# CH32V203F6P6-R0.net
KiCad netlist of a schematic drawn in Altium Designer
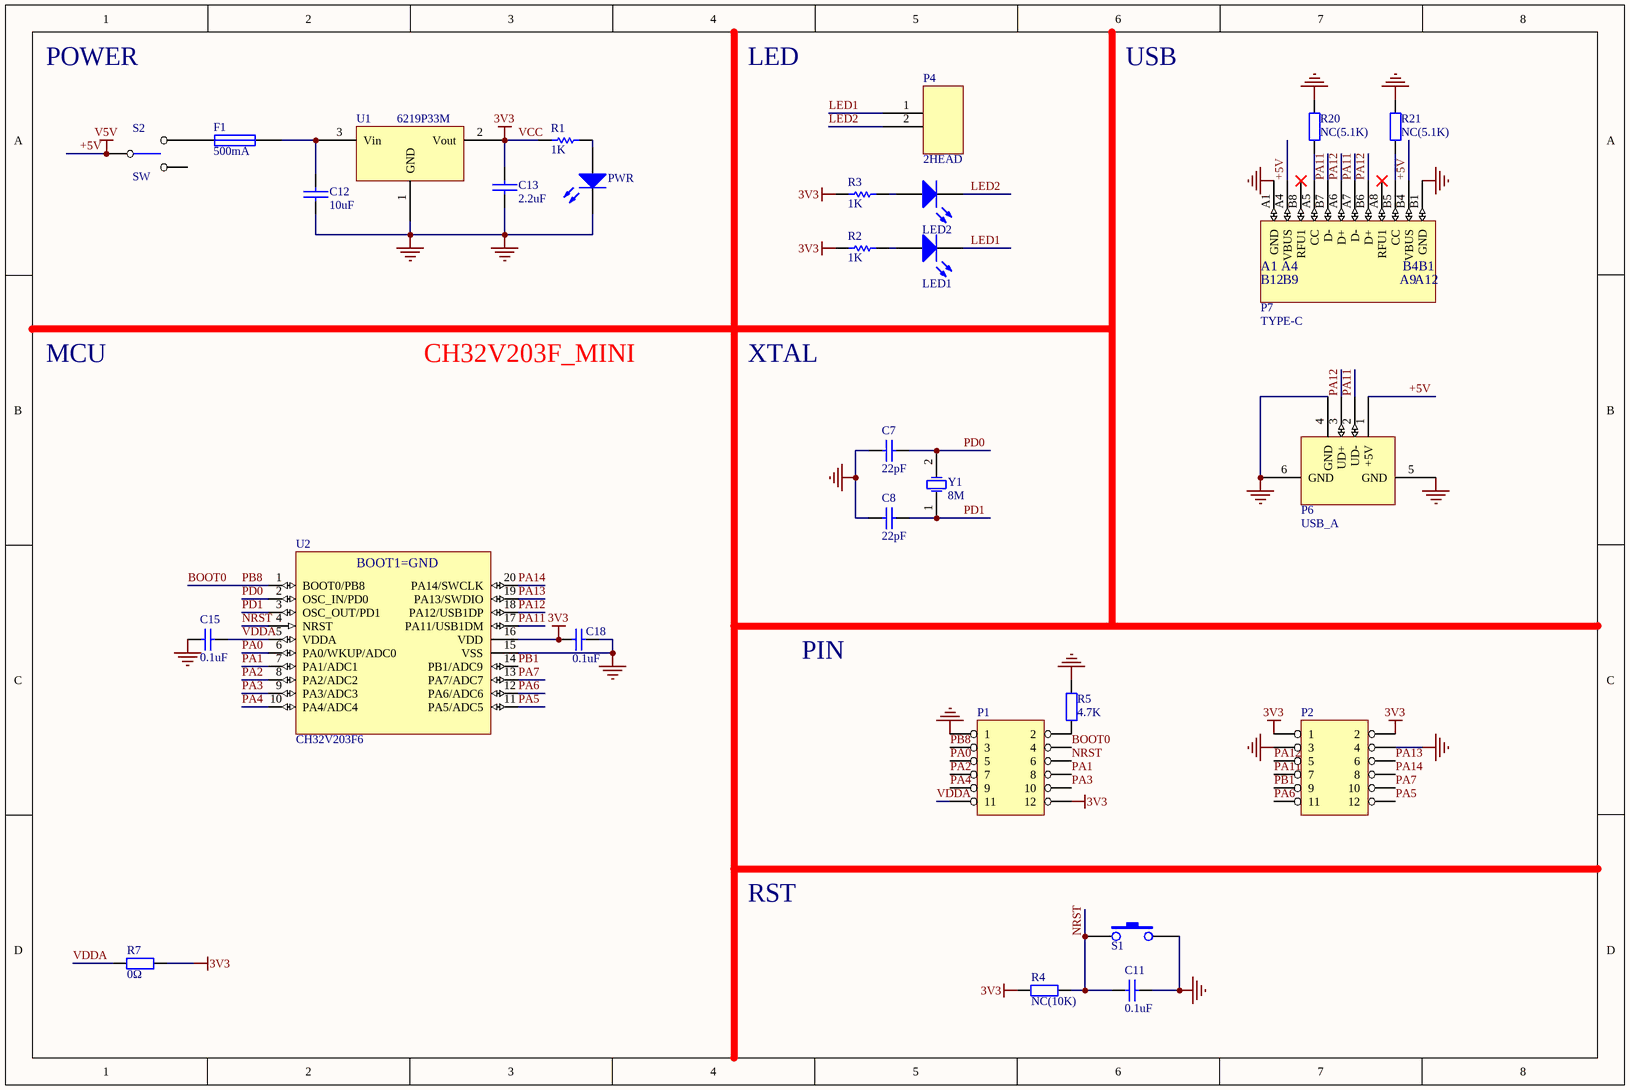
[diagram p0: CH32V203F6P6-R0.SchDoc]

(export (version "E")
  (design (tool "Eeschema 10.0.6"))
  (components
    (comp (ref "C7")
      (value "22pF")
      (footprint "0603_C")
      (description "Capacitor")
      (fields (field (name "PUBLISHER") "Altium Limited"))
      (libsource (lib "*") (part "Cap"))
    )
    (comp (ref "C8")
      (value "22pF")
      (footprint "0603_C")
      (description "Capacitor")
      (fields (field (name "PUBLISHER") "Altium Limited"))
      (libsource (lib "*") (part "Cap"))
    )
    (comp (ref "C11")
      (value "0.1uF")
      (footprint "0603_C")
      (description "Capacitor")
      (fields (field (name "PUBLISHER") "Altium Limited"))
      (libsource (lib "*") (part "Cap"))
    )
    (comp (ref "C12")
      (value "10uF")
      (footprint "3216_C")
      (description "Capacitor")
      (libsource (lib "wch_sch_others") (part "CAP"))
    )
    (comp (ref "C13")
      (value "2.2uF")
      (footprint "0603_C")
      (description "Capacitor")
      (libsource (lib "wch_sch_others") (part "CAP"))
    )
    (comp (ref "C15")
      (value "0.1uF")
      (footprint "0603_C")
      (description "Capacitor")
      (fields (field (name "PUBLISHER") "Altium Limited"))
      (libsource (lib "*") (part "Cap"))
    )
    (comp (ref "C18")
      (value "0.1uF")
      (footprint "0603_C")
      (description "Capacitor")
      (fields (field (name "PUBLISHER") "Altium Limited"))
      (libsource (lib "*") (part "Cap"))
    )
    (comp (ref "F1")
      (value "500mA")
      (footprint "0603")
      (description "Fuse")
      (libsource (lib "*") (part "FUSE1"))
    )
    (comp (ref "LED1")
      (value "LED1   blue")
      (footprint "0603+")
      (description "Typical INFRARED GaAs LED")
      (fields (field (name "PUBLISHER") "Altium Limited"))
      (libsource (lib "*") (part "LED0"))
    )
    (comp (ref "LED2")
      (value "LED2  blue")
      (footprint "0603+")
      (description "Typical INFRARED GaAs LED")
      (fields (field (name "PUBLISHER") "Altium Limited"))
      (libsource (lib "*") (part "LED0"))
    )
    (comp (ref "P1")
      (value "HEADER 6x2")
      (footprint "MYPCB:IDC12-2.54mm")
      (description "Header, 6-Pin, Dual row")
      (libsource (lib "wch_sch_others") (part "HEADER 6x2"))
    )
    (comp (ref "P2")
      (value "HEADER 6x2")
      (footprint "MYPCB:IDC12-2.54mm")
      (description "Header, 6-Pin, Dual row")
      (libsource (lib "wch_sch_others") (part "HEADER 6x2"))
    )
    (comp (ref "P4") (value "2HEAD") (footprint "SIP2-2.54mm") (libsource (lib "*") (part "2HEAD")))
    (comp (ref "P6")
      (value "USB_A")
      (footprint "USBAF")
      (description "USB Port")
      (libsource (lib "*") (part "USB"))
    )
    (comp (ref "P7")
      (value "TYPE-C")
      (footprint "TYPE-C-Receptacle-2.0")
      (libsource (lib "*") (part "TYPE-C1"))
    )
    (comp (ref "PWR")
      (value "POWER  red")
      (footprint "0603+")
      (description "Typical INFRARED GaAs LED")
      (fields (field (name "PUBLISHER") "Altium Limited"))
      (libsource (lib "*") (part "LED0"))
    )
    (comp (ref "R1")
      (value "1K")
      (footprint "0603")
      (description "Semiconductor Resistor")
      (fields (field (name "PUBLISHER") "Altium Limited"))
      (libsource (lib "*") (part "Res Semi"))
    )
    (comp (ref "R2")
      (value "1K")
      (footprint "0603")
      (description "Semiconductor Resistor")
      (fields (field (name "PUBLISHER") "Altium Limited"))
      (libsource (lib "*") (part "Res Semi"))
    )
    (comp (ref "R3")
      (value "1K")
      (footprint "0603")
      (description "Semiconductor Resistor")
      (fields (field (name "PUBLISHER") "Altium Limited"))
      (libsource (lib "*") (part "Res Semi"))
    )
    (comp (ref "R4")
      (value "NC(10K)")
      (footprint "0603")
      (description "Resistor")
      (fields (field (name "PUBLISHER") "Altium Limited"))
      (libsource (lib "") (part "Res2_1"))
    )
    (comp (ref "R5")
      (value "4.7K")
      (footprint "0603")
      (description "Resistor")
      (fields (field (name "PUBLISHER") "Altium Limited"))
      (libsource (lib "*") (part "Res2"))
    )
    (comp (ref "R7")
      (value "0Ω")
      (footprint "0603")
      (description "Resistor")
      (fields (field (name "PUBLISHER") "Altium Limited"))
      (libsource (lib "") (part "Res2_1"))
    )
    (comp (ref "R20")
      (value "NC(5.1K)")
      (footprint "0603")
      (description "Resistor")
      (libsource (lib "Miscellaneous Devices") (part "Res2"))
    )
    (comp (ref "R21")
      (value "NC(5.1K)")
      (footprint "0603")
      (description "Resistor")
      (libsource (lib "Miscellaneous Devices") (part "Res2"))
    )
    (comp (ref "S1") (value "NRST") (footprint "SMD_6.1x3.65x2.5mm-KEY") (libsource (lib "*") (part "KEY")))
    (comp (ref "S2") (value "SW") (footprint "KEY2") (libsource (lib "*") (part "SW")))
    (comp (ref "U1")
      (value "6219P33M")
      (footprint "SOT-23")
      (libsource (lib "wch_sch_others") (part "6219P33M"))
    )
    (comp (ref "U2")
      (value "CH32V203F6")
      (footprint "TSSOP20")
      (description "RISC-V LMD-MCU, 144MHz, USB FS, CAN, Mul-ADC,OPA")
      (libsource (lib "CHXXX") (part "CH32V203F6"))
    )
    (comp (ref "Y1")
      (value "8M")
      (footprint "XT_AT49")
      (description "Crystal Oscillator")
      (fields (field (name "PUBLISHER") "Altium Limited"))
      (libsource (lib "*") (part "XTAL"))
    )
  )
  (nets
    (net (code "2") (name "/BOOT0") (class "Default")
      (node (ref "P1") (pin "3") (pinfunction "3_3") (pintype "passive"))
      (node (ref "P1") (pin "4") (pinfunction "4_4") (pintype "passive"))
      (node (ref "U2") (pin "1") (pinfunction "BOOT0/PB8_1") (pintype "bidirectional"))
    )
    (net (code "3") (name "/LED1") (class "Default")
      (node (ref "LED1") (pin "2") (pinfunction "K_2") (pintype "passive"))
      (node (ref "P4") (pin "1") (pintype "passive"))
    )
    (net (code "4") (name "/LED2") (class "Default")
      (node (ref "LED2") (pin "2") (pinfunction "K_2") (pintype "passive"))
      (node (ref "P4") (pin "2") (pintype "passive"))
    )
    (net (code "5") (name "/NRST") (class "Default")
      (node (ref "C11") (pin "2") (pinfunction "2_2") (pintype "passive"))
      (node (ref "P1") (pin "6") (pinfunction "6_6") (pintype "passive"))
      (node (ref "R4") (pin "1") (pinfunction "1_1") (pintype "passive"))
      (node (ref "S1") (pin "1") (pinfunction "1_1") (pintype "passive"))
      (node (ref "U2") (pin "4") (pinfunction "NRST_4") (pintype "input"))
    )
    (net (code "6") (name "/PA0") (class "Default")
      (node (ref "P1") (pin "5") (pinfunction "5_5") (pintype "passive"))
      (node (ref "U2") (pin "6") (pinfunction "PA0/WKUP/ADC0_6") (pintype "bidirectional"))
    )
    (net (code "7") (name "/PA1") (class "Default")
      (node (ref "P1") (pin "8") (pinfunction "8_8") (pintype "passive"))
      (node (ref "U2") (pin "7") (pinfunction "PA1/ADC1_7") (pintype "bidirectional"))
    )
    (net (code "8") (name "/PA2") (class "Default")
      (node (ref "P1") (pin "7") (pinfunction "7_7") (pintype "passive"))
      (node (ref "U2") (pin "8") (pinfunction "PA2/ADC2_8") (pintype "bidirectional"))
    )
    (net (code "9") (name "/PA3") (class "Default")
      (node (ref "P1") (pin "10") (pinfunction "10_10") (pintype "passive"))
      (node (ref "U2") (pin "9") (pinfunction "PA3/ADC3_9") (pintype "bidirectional"))
    )
    (net (code "10") (name "/PA4") (class "Default")
      (node (ref "P1") (pin "9") (pinfunction "9_9") (pintype "passive"))
      (node (ref "U2") (pin "10") (pinfunction "PA4/ADC4_10") (pintype "bidirectional"))
    )
    (net (code "11") (name "/PA5") (class "Default")
      (node (ref "P2") (pin "12") (pinfunction "12_12") (pintype "passive"))
      (node (ref "U2") (pin "11") (pinfunction "PA5/ADC5_11") (pintype "bidirectional"))
    )
    (net (code "12") (name "/PA6") (class "Default")
      (node (ref "P2") (pin "11") (pinfunction "11_11") (pintype "passive"))
      (node (ref "U2") (pin "12") (pinfunction "PA6/ADC6_12") (pintype "bidirectional"))
    )
    (net (code "13") (name "/PA7") (class "Default")
      (node (ref "P2") (pin "10") (pinfunction "10_10") (pintype "passive"))
      (node (ref "U2") (pin "13") (pinfunction "PA7/ADC7_13") (pintype "bidirectional"))
    )
    (net (code "14") (name "/PA11") (class "Default")
      (node (ref "P2") (pin "7") (pinfunction "7_7") (pintype "passive"))
      (node (ref "P6") (pin "2") (pinfunction "UD-_2") (pintype "bidirectional"))
      (node (ref "P7") (pin "A7") (pinfunction "D-_A7") (pintype "bidirectional"))
      (node (ref "P7") (pin "B7") (pinfunction "D-_B7") (pintype "bidirectional"))
      (node (ref "U2") (pin "17") (pinfunction "PA11/USB1DM_17") (pintype "bidirectional"))
    )
    (net (code "15") (name "/PA12") (class "Default")
      (node (ref "P2") (pin "5") (pinfunction "5_5") (pintype "passive"))
      (node (ref "P6") (pin "3") (pinfunction "UD+_3") (pintype "bidirectional"))
      (node (ref "P7") (pin "A6") (pinfunction "D+_A6") (pintype "bidirectional"))
      (node (ref "P7") (pin "B6") (pinfunction "D+_B6") (pintype "bidirectional"))
      (node (ref "U2") (pin "18") (pinfunction "PA12/USB1DP_18") (pintype "bidirectional"))
    )
    (net (code "16") (name "/PA13") (class "Default")
      (node (ref "P2") (pin "6") (pinfunction "6_6") (pintype "passive"))
      (node (ref "U2") (pin "19") (pinfunction "PA13/SWDIO_19") (pintype "bidirectional"))
    )
    (net (code "17") (name "/PA14") (class "Default")
      (node (ref "P2") (pin "8") (pinfunction "8_8") (pintype "passive"))
      (node (ref "U2") (pin "20") (pinfunction "PA14/SWCLK_20") (pintype "bidirectional"))
    )
    (net (code "18") (name "/PB1") (class "Default")
      (node (ref "P2") (pin "9") (pinfunction "9_9") (pintype "passive"))
      (node (ref "U2") (pin "14") (pinfunction "PB1/ADC9_14") (pintype "bidirectional"))
    )
    (net (code "19") (name "/PD0") (class "Default")
      (node (ref "C7") (pin "2") (pinfunction "2_2") (pintype "passive"))
      (node (ref "U2") (pin "2") (pinfunction "OSC_IN/PD0_2") (pintype "bidirectional"))
      (node (ref "Y1") (pin "2") (pinfunction "OSC2_2") (pintype "passive"))
    )
    (net (code "20") (name "/PD1") (class "Default")
      (node (ref "C8") (pin "2") (pinfunction "2_2") (pintype "passive"))
      (node (ref "U2") (pin "3") (pinfunction "OSC_OUT/PD1_3") (pintype "bidirectional"))
      (node (ref "Y1") (pin "1") (pinfunction "OSC1_1") (pintype "passive"))
    )
    (net (code "21") (name "/VDDA") (class "Default")
      (node (ref "C15") (pin "1") (pinfunction "1_1") (pintype "passive"))
      (node (ref "P1") (pin "11") (pinfunction "11_11") (pintype "passive"))
      (node (ref "R7") (pin "2") (pinfunction "2_2") (pintype "passive"))
      (node (ref "U2") (pin "5") (pinfunction "VDDA_5") (pintype "bidirectional"))
    )
    (net (code "22") (name "3V3") (class "Default")
      (node (ref "C13") (pin "2") (pinfunction "2_2") (pintype "passive"))
      (node (ref "C18") (pin "2") (pinfunction "2_2") (pintype "passive"))
      (node (ref "P1") (pin "12") (pinfunction "12_12") (pintype "passive"))
      (node (ref "P2") (pin "1") (pinfunction "1_1") (pintype "passive"))
      (node (ref "P2") (pin "2") (pinfunction "2_2") (pintype "passive"))
      (node (ref "R1") (pin "2") (pinfunction "2_2") (pintype "passive"))
      (node (ref "R2") (pin "1") (pinfunction "1_1") (pintype "passive"))
      (node (ref "R3") (pin "1") (pinfunction "1_1") (pintype "passive"))
      (node (ref "R4") (pin "2") (pinfunction "2_2") (pintype "passive"))
      (node (ref "R7") (pin "1") (pinfunction "1_1") (pintype "passive"))
      (node (ref "U1") (pin "2") (pinfunction "Vout_2") (pintype "passive"))
      (node (ref "U2") (pin "16") (pinfunction "VDD_16") (pintype "power_in"))
    )
    (net (code "23") (name "GND") (class "Default")
      (node (ref "C11") (pin "1") (pinfunction "1_1") (pintype "passive"))
      (node (ref "C12") (pin "2") (pinfunction "2_2") (pintype "passive"))
      (node (ref "C13") (pin "1") (pinfunction "1_1") (pintype "passive"))
      (node (ref "C15") (pin "2") (pinfunction "2_2") (pintype "passive"))
      (node (ref "C18") (pin "1") (pinfunction "1_1") (pintype "passive"))
      (node (ref "C7") (pin "1") (pinfunction "1_1") (pintype "passive"))
      (node (ref "C8") (pin "1") (pinfunction "1_1") (pintype "passive"))
      (node (ref "P1") (pin "1") (pinfunction "1_1") (pintype "passive"))
      (node (ref "P2") (pin "3") (pinfunction "3_3") (pintype "passive"))
      (node (ref "P2") (pin "4") (pinfunction "4_4") (pintype "passive"))
      (node (ref "P6") (pin "4") (pinfunction "GND_4") (pintype "power_in"))
      (node (ref "P6") (pin "5") (pinfunction "GND_5") (pintype "power_in"))
      (node (ref "P6") (pin "6") (pinfunction "GND_6") (pintype "power_in"))
      (node (ref "P7") (pin "A1") (pinfunction "GND_A1") (pintype "bidirectional"))
      (node (ref "P7") (pin "B1") (pinfunction "GND_B1") (pintype "bidirectional"))
      (node (ref "PWR") (pin "2") (pinfunction "K_2") (pintype "passive"))
      (node (ref "R20") (pin "2") (pinfunction "2_2") (pintype "passive"))
      (node (ref "R21") (pin "2") (pinfunction "2_2") (pintype "passive"))
      (node (ref "R5") (pin "2") (pinfunction "2_2") (pintype "passive"))
      (node (ref "S1") (pin "2") (pinfunction "2_2") (pintype "passive"))
      (node (ref "U1") (pin "1") (pinfunction "GND_1") (pintype "passive"))
      (node (ref "U2") (pin "15") (pinfunction "VSS_15") (pintype "power_in"))
    )
    (net (code "24") (name "Net-(F1-Pad1)") (class "Default")
      (node (ref "F1") (pin "1") (pinfunction "1_1") (pintype "passive"))
      (node (ref "S2") (pin "3") (pinfunction "3_3") (pintype "passive"))
    )
    (net (code "25") (name "Net-(LED1-A)") (class "Default")
      (node (ref "LED1") (pin "1") (pinfunction "A_1") (pintype "passive"))
      (node (ref "R2") (pin "2") (pinfunction "2_2") (pintype "passive"))
    )
    (net (code "26") (name "Net-(LED2-A)") (class "Default")
      (node (ref "LED2") (pin "1") (pinfunction "A_1") (pintype "passive"))
      (node (ref "R3") (pin "2") (pinfunction "2_2") (pintype "passive"))
    )
    (net (code "27") (name "Net-(P1-Pad2)") (class "Default")
      (node (ref "P1") (pin "2") (pinfunction "2_2") (pintype "passive"))
      (node (ref "R5") (pin "1") (pinfunction "1_1") (pintype "passive"))
    )
    (net (code "28") (name "Net-(P7-CC-PadA5)") (class "Default")
      (node (ref "P7") (pin "A5") (pinfunction "CC_A5") (pintype "bidirectional"))
      (node (ref "R20") (pin "1") (pinfunction "1_1") (pintype "passive"))
    )
    (net (code "29") (name "Net-(P7-CC-PadB5)") (class "Default")
      (node (ref "P7") (pin "B5") (pinfunction "CC_B5") (pintype "bidirectional"))
      (node (ref "R21") (pin "1") (pinfunction "1_1") (pintype "passive"))
    )
    (net (code "30") (name "Net-(PWR-A)") (class "Default")
      (node (ref "PWR") (pin "1") (pinfunction "A_1") (pintype "passive"))
      (node (ref "R1") (pin "1") (pinfunction "1_1") (pintype "passive"))
    )
    (net (code "31") (name "Net-(U1-Vin)") (class "Default")
      (node (ref "C12") (pin "1") (pinfunction "1_1") (pintype "passive"))
      (node (ref "F1") (pin "2") (pinfunction "2_2") (pintype "passive"))
      (node (ref "U1") (pin "3") (pinfunction "Vin_3") (pintype "passive"))
    )
    (net (code "32") (name "V5V") (class "Default")
      (node (ref "P6") (pin "1") (pinfunction "+5V_1") (pintype "power_in"))
      (node (ref "P7") (pin "A4") (pinfunction "VBUS_A4") (pintype "bidirectional"))
      (node (ref "P7") (pin "B4") (pinfunction "VBUS_B4") (pintype "bidirectional"))
      (node (ref "S2") (pin "1") (pinfunction "1_1") (pintype "passive"))
    )
    (net (code "33") (name "unconnected-(P7-RFU1-PadA8)") (class "Default")
      (node (ref "P7") (pin "A8") (pinfunction "RFU1_A8") (pintype "bidirectional+no_connect"))
    )
    (net (code "34") (name "unconnected-(P7-RFU1-PadB8)") (class "Default")
      (node (ref "P7") (pin "B8") (pinfunction "RFU1_B8") (pintype "bidirectional+no_connect"))
    )
    (net (code "35") (name "unconnected-(S2-Pad2)") (class "Default")
      (node (ref "S2") (pin "2") (pinfunction "2_2") (pintype "passive"))
    )
  )
)
